# Chess_Clock_Larger.net
KiCad netlist of a schematic drawn in EAGLE
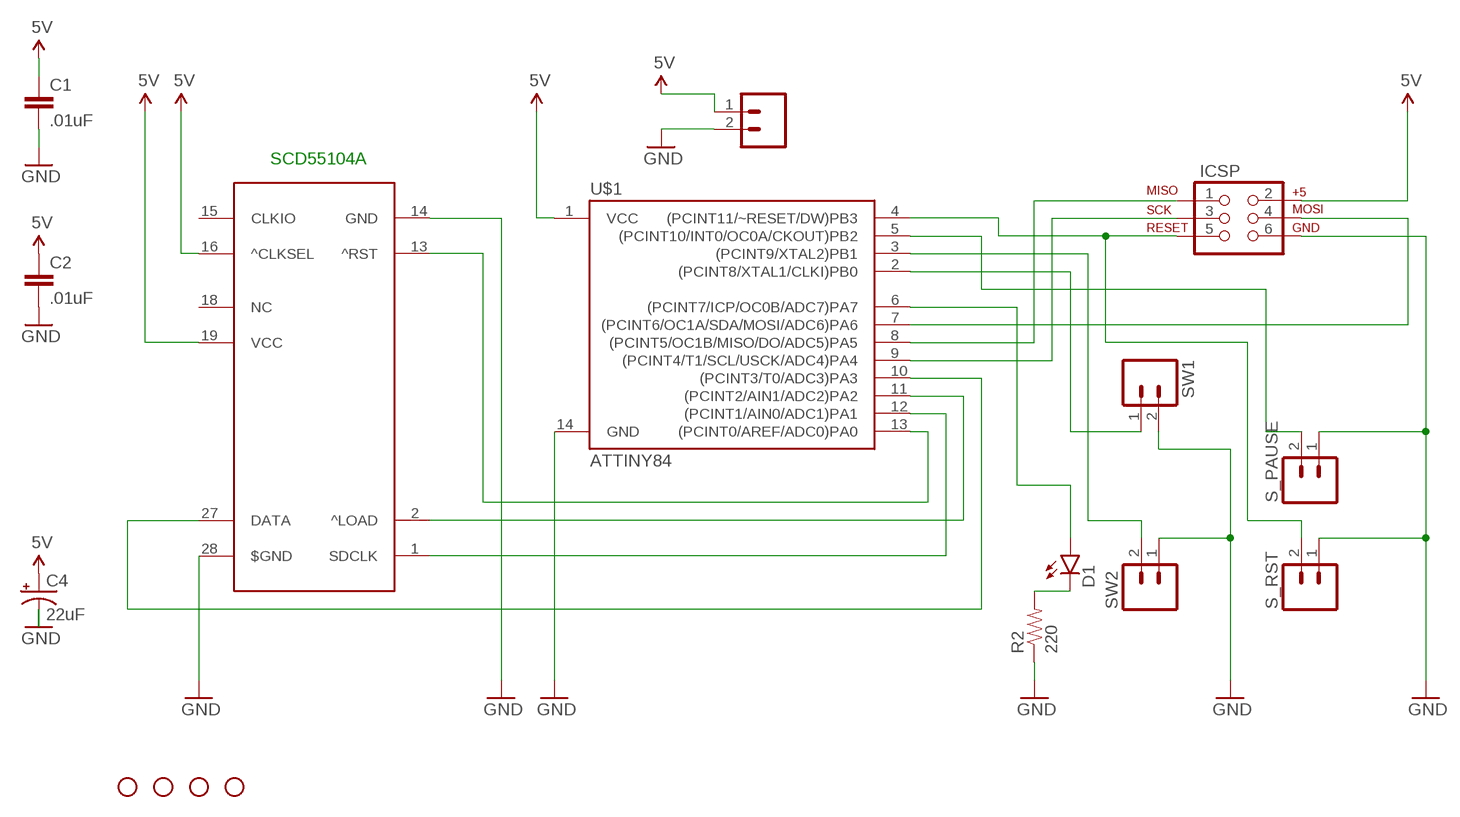
[diagram p0: schematic, sheet 1]

(export (version "E")
  (design (tool "Eeschema 10.0.6"))
  (components
    (comp (ref "C1")
      (value ".01uF")
      (footprint "eagle-import:CAP-PTH-SMALL")
      (libsource (lib "eagle-import") (part "CAPPTH"))
    )
    (comp (ref "C2")
      (value ".01uF")
      (footprint "eagle-import:CAP-PTH-SMALL")
      (libsource (lib "eagle-import") (part "CAPPTH"))
    )
    (comp (ref "C4")
      (value "22uF")
      (footprint "eagle-import:CPOL-RADIAL-10UF-25V")
      (libsource (lib "eagle-import") (part "CAP_POLPTH2"))
    )
    (comp (ref "D1")
      (value "LED5MM")
      (footprint "eagle-import:LED5MM")
      (libsource (lib "eagle-import") (part "LED5MM"))
    )
    (comp (ref "ICSP")
      (value "AVR_SPI_PRG_6PTH")
      (footprint "eagle-import:2X3")
      (libsource (lib "eagle-import") (part "AVR_SPI_PRG_6PTH"))
    )
    (comp (ref "R2")
      (value "220")
      (footprint "eagle-import:1206")
      (libsource (lib "eagle-import") (part "RESISTOR1206"))
    )
    (comp (ref "SCD55104A")
      (value "SCD_55104A")
      (footprint "eagle-import:SCD55104A")
      (libsource (lib "eagle-import") (part "SCD_55104A"))
    )
    (comp (ref "STANDOFF1")
      (value "STAND-OFF")
      (footprint "eagle-import:STAND-OFF")
      (libsource (lib "eagle-import") (part "STAND-OFF"))
    )
    (comp (ref "STANDOFF2")
      (value "STAND-OFF")
      (footprint "eagle-import:STAND-OFF")
      (libsource (lib "eagle-import") (part "STAND-OFF"))
    )
    (comp (ref "STANDOFF3")
      (value "STAND-OFF")
      (footprint "eagle-import:STAND-OFF")
      (libsource (lib "eagle-import") (part "STAND-OFF"))
    )
    (comp (ref "STANDOFF4")
      (value "STAND-OFF")
      (footprint "eagle-import:STAND-OFF")
      (libsource (lib "eagle-import") (part "STAND-OFF"))
    )
    (comp (ref "SW1")
      (value "M02PTH")
      (footprint "eagle-import:1X02")
      (libsource (lib "eagle-import") (part "M02PTH"))
    )
    (comp (ref "SW2")
      (value "M02PTH")
      (footprint "eagle-import:1X02")
      (libsource (lib "eagle-import") (part "M02PTH"))
    )
    (comp (ref "SW3")
      (value "M02PTH")
      (footprint "eagle-import:1X02")
      (libsource (lib "eagle-import") (part "M02PTH"))
    )
    (comp (ref "S_PAUSE")
      (value "M02PTH")
      (footprint "eagle-import:1X02")
      (libsource (lib "eagle-import") (part "M02PTH"))
    )
    (comp (ref "S_RST")
      (value "M02PTH")
      (footprint "eagle-import:1X02")
      (libsource (lib "eagle-import") (part "M02PTH"))
    )
    (comp (ref "U$1")
      (value "ATTINY84")
      (footprint "eagle-import:SO14")
      (libsource (lib "eagle-import") (part "ATTINY84"))
    )
  )
  (nets
    (net (code "1") (name "5V") (class "Default")
      (node (ref "C1") (pin "1") (pinfunction "1_1") (pintype "passive"))
      (node (ref "C2") (pin "1") (pinfunction "1_1") (pintype "passive"))
      (node (ref "C4") (pin "1") (pinfunction "+_1") (pintype "passive"))
      (node (ref "ICSP") (pin "2") (pinfunction "2_2") (pintype "passive"))
      (node (ref "SCD55104A") (pin "16") (pinfunction "^CLKSEL_16") (pintype "bidirectional"))
      (node (ref "SCD55104A") (pin "19") (pinfunction "VCC_19") (pintype "bidirectional"))
      (node (ref "SW3") (pin "1") (pinfunction "1_1") (pintype "passive"))
      (node (ref "U$1") (pin "1") (pinfunction "VCC_1") (pintype "bidirectional"))
    )
    (net (code "2") (name "GND") (class "Default")
      (node (ref "C1") (pin "2") (pinfunction "2_2") (pintype "passive"))
      (node (ref "C2") (pin "2") (pinfunction "2_2") (pintype "passive"))
      (node (ref "C4") (pin "2") (pinfunction "-_2") (pintype "passive"))
      (node (ref "ICSP") (pin "6") (pinfunction "6_6") (pintype "passive"))
      (node (ref "R2") (pin "1") (pinfunction "1_1") (pintype "passive"))
      (node (ref "SCD55104A") (pin "14") (pinfunction "GND_14") (pintype "bidirectional"))
      (node (ref "SCD55104A") (pin "28") (pinfunction "$GND_28") (pintype "bidirectional"))
      (node (ref "SW1") (pin "2") (pinfunction "2_2") (pintype "passive"))
      (node (ref "SW2") (pin "1") (pinfunction "1_1") (pintype "passive"))
      (node (ref "SW3") (pin "2") (pinfunction "2_2") (pintype "passive"))
      (node (ref "S_PAUSE") (pin "1") (pinfunction "1_1") (pintype "passive"))
      (node (ref "S_RST") (pin "1") (pinfunction "1_1") (pintype "passive"))
      (node (ref "U$1") (pin "14") (pinfunction "GND_14") (pintype "bidirectional"))
    )
    (net (code "3") (name "Net-(D1-C)") (class "Default")
      (node (ref "D1") (pin "K") (pinfunction "C_K") (pintype "passive"))
      (node (ref "R2") (pin "2") (pinfunction "2_2") (pintype "passive"))
    )
    (net (code "4") (name "Net-(SCD55104A-DATA)") (class "Default")
      (node (ref "SCD55104A") (pin "27") (pinfunction "DATA_27") (pintype "bidirectional"))
      (node (ref "U$1") (pin "10") (pinfunction "(PCINT3/T0/ADC3)PA3_10") (pintype "bidirectional"))
    )
    (net (code "5") (name "Net-(SCD55104A-SDCLK)") (class "Default")
      (node (ref "SCD55104A") (pin "1") (pinfunction "SDCLK_1") (pintype "bidirectional"))
      (node (ref "U$1") (pin "12") (pinfunction "(PCINT1/AIN0/ADC1)PA1_12") (pintype "bidirectional"))
    )
    (net (code "6") (name "Net-(SCD55104A-^LOAD)") (class "Default")
      (node (ref "SCD55104A") (pin "2") (pinfunction "^LOAD_2") (pintype "bidirectional"))
      (node (ref "U$1") (pin "11") (pinfunction "(PCINT2/AIN1/ADC2)PA2_11") (pintype "bidirectional"))
    )
    (net (code "7") (name "Net-(SCD55104A-^RST)") (class "Default")
      (node (ref "SCD55104A") (pin "13") (pinfunction "^RST_13") (pintype "bidirectional"))
      (node (ref "U$1") (pin "13") (pinfunction "(PCINT0/AREF/ADC0)PA0_13") (pintype "bidirectional"))
    )
    (net (code "8") (name "Net-(U$1-(PCINT4{slash}T1{slash}SCL{slash}USCK{slash}ADC4)PA4)") (class "Default")
      (node (ref "ICSP") (pin "3") (pinfunction "3_3") (pintype "passive"))
      (node (ref "U$1") (pin "9") (pinfunction "(PCINT4/T1/SCL/USCK/ADC4)PA4_9") (pintype "bidirectional"))
    )
    (net (code "9") (name "Net-(U$1-(PCINT5{slash}OC1B{slash}MISO{slash}DO{slash}ADC5)PA5)") (class "Default")
      (node (ref "ICSP") (pin "1") (pinfunction "1_1") (pintype "passive"))
      (node (ref "U$1") (pin "8") (pinfunction "(PCINT5/OC1B/MISO/DO/ADC5)PA5_8") (pintype "bidirectional"))
    )
    (net (code "10") (name "Net-(U$1-(PCINT6{slash}OC1A{slash}SDA{slash}MOSI{slash}ADC6)PA6)") (class "Default")
      (node (ref "ICSP") (pin "4") (pinfunction "4_4") (pintype "passive"))
      (node (ref "U$1") (pin "7") (pinfunction "(PCINT6/OC1A/SDA/MOSI/ADC6)PA6_7") (pintype "bidirectional"))
    )
    (net (code "11") (name "Net-(U$1-(PCINT7{slash}ICP{slash}OC0B{slash}ADC7)PA7)") (class "Default")
      (node (ref "D1") (pin "A") (pinfunction "A_A") (pintype "passive"))
      (node (ref "U$1") (pin "6") (pinfunction "(PCINT7/ICP/OC0B/ADC7)PA7_6") (pintype "bidirectional"))
    )
    (net (code "12") (name "Net-(U$1-(PCINT8{slash}XTAL1{slash}CLKI)PB0)") (class "Default")
      (node (ref "SW1") (pin "1") (pinfunction "1_1") (pintype "passive"))
      (node (ref "U$1") (pin "2") (pinfunction "(PCINT8/XTAL1/CLKI)PB0_2") (pintype "bidirectional"))
    )
    (net (code "13") (name "Net-(U$1-(PCINT9{slash}XTAL2)PB1)") (class "Default")
      (node (ref "SW2") (pin "2") (pinfunction "2_2") (pintype "passive"))
      (node (ref "U$1") (pin "3") (pinfunction "(PCINT9/XTAL2)PB1_3") (pintype "bidirectional"))
    )
    (net (code "14") (name "Net-(U$1-(PCINT10{slash}INT0{slash}OC0A{slash}CKOUT)PB2)") (class "Default")
      (node (ref "S_PAUSE") (pin "2") (pinfunction "2_2") (pintype "passive"))
      (node (ref "U$1") (pin "5") (pinfunction "(PCINT10/INT0/OC0A/CKOUT)PB2_5") (pintype "bidirectional"))
    )
    (net (code "15") (name "Net-(U$1-(PCINT11{slash}~{RESET{slash}DW})PB3)") (class "Default")
      (node (ref "ICSP") (pin "5") (pinfunction "5_5") (pintype "passive"))
      (node (ref "S_RST") (pin "2") (pinfunction "2_2") (pintype "passive"))
      (node (ref "U$1") (pin "4") (pinfunction "(PCINT11/~{RESET/DW})PB3_4") (pintype "bidirectional"))
    )
    (net (code "16") (name "unconnected-(SCD55104A-CLKIO-Pad15)") (class "Default")
      (node (ref "SCD55104A") (pin "15") (pinfunction "CLKIO_15") (pintype "bidirectional"))
    )
    (net (code "17") (name "unconnected-(SCD55104A-NC-Pad18)") (class "Default")
      (node (ref "SCD55104A") (pin "18") (pinfunction "NC_18") (pintype "bidirectional"))
    )
  )
)
